# Shield.net
KiCad netlist of a schematic drawn in EAGLE
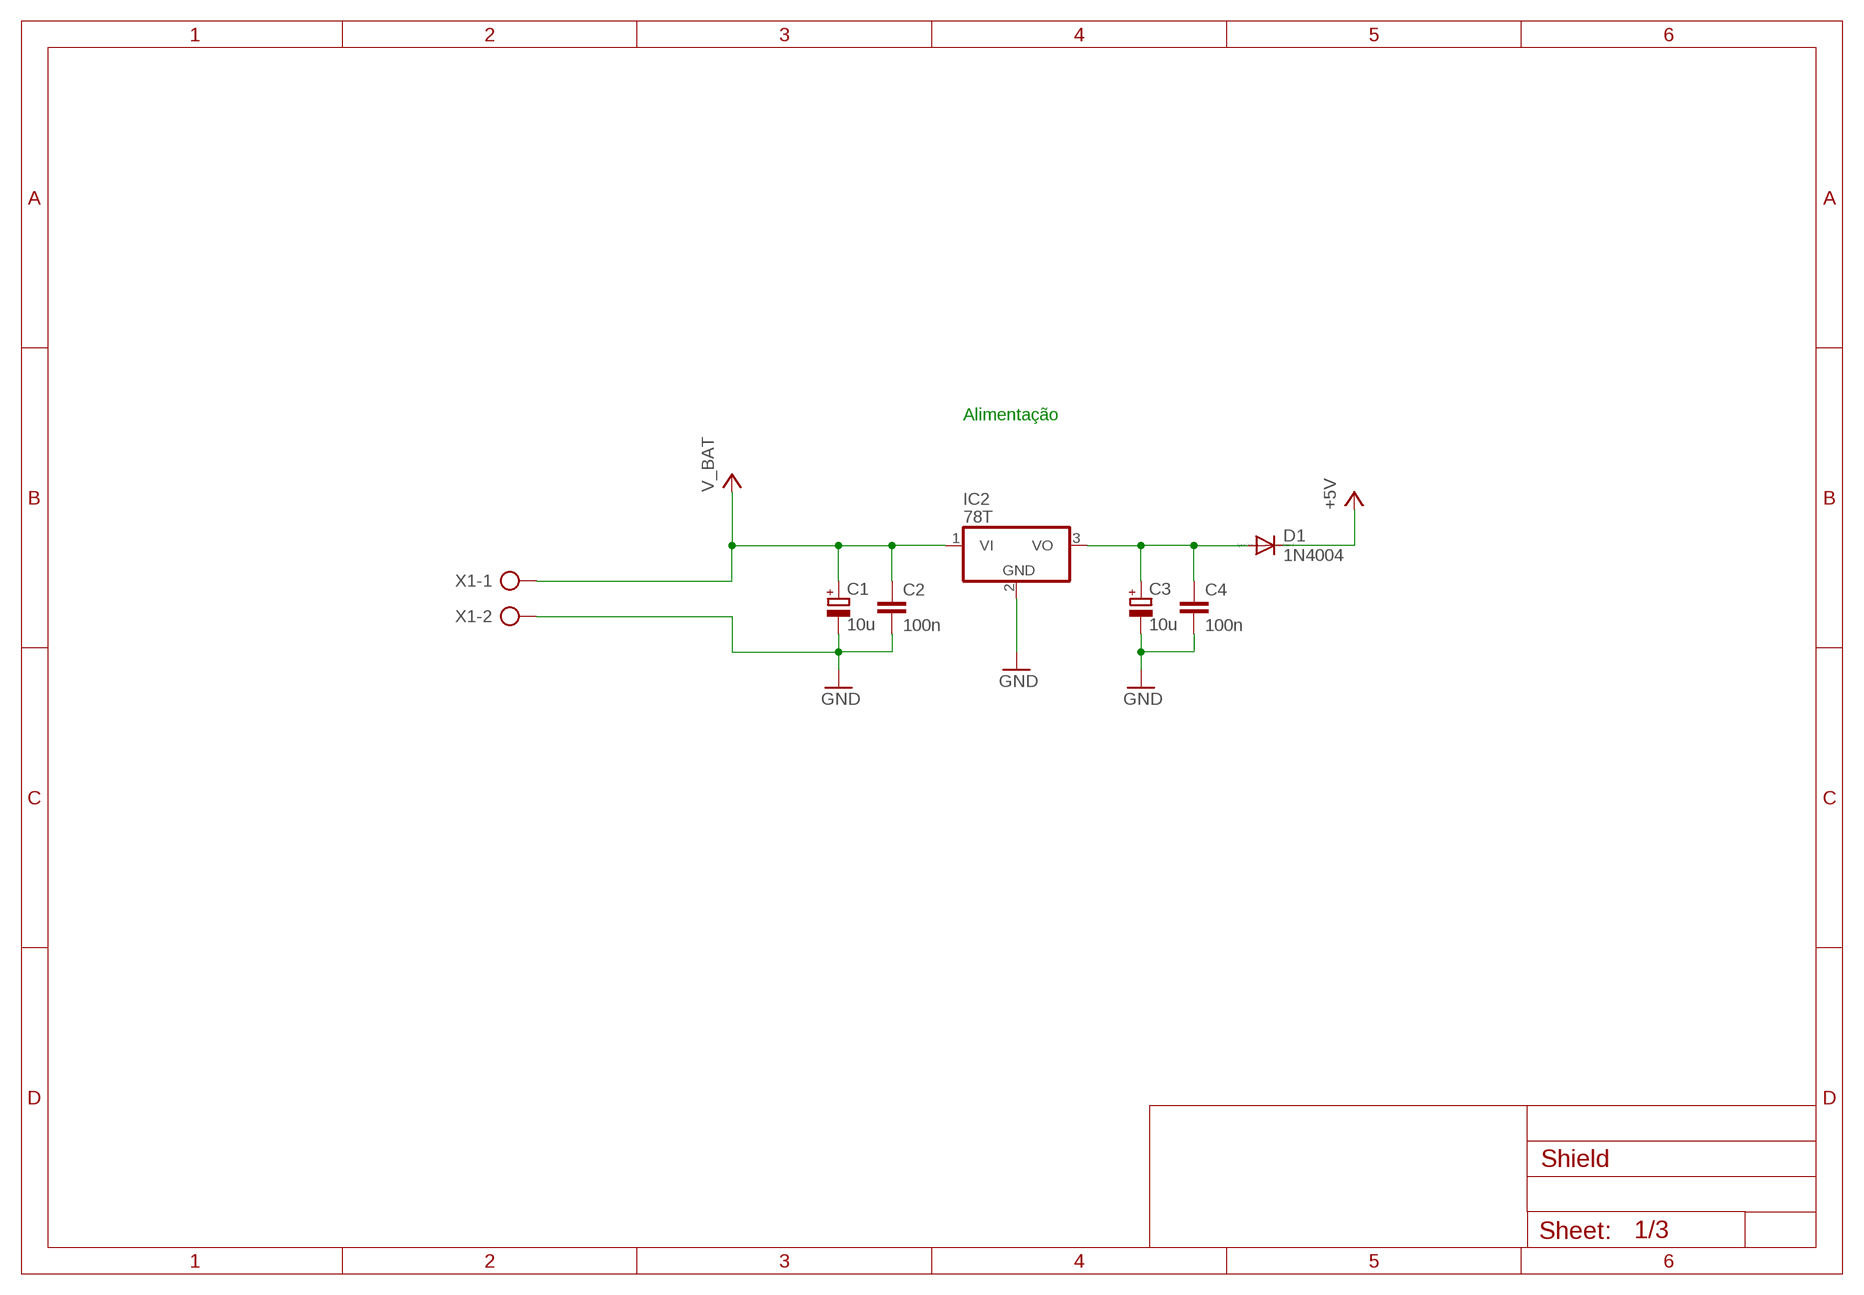
[diagram p0: schematic, sheet 1]
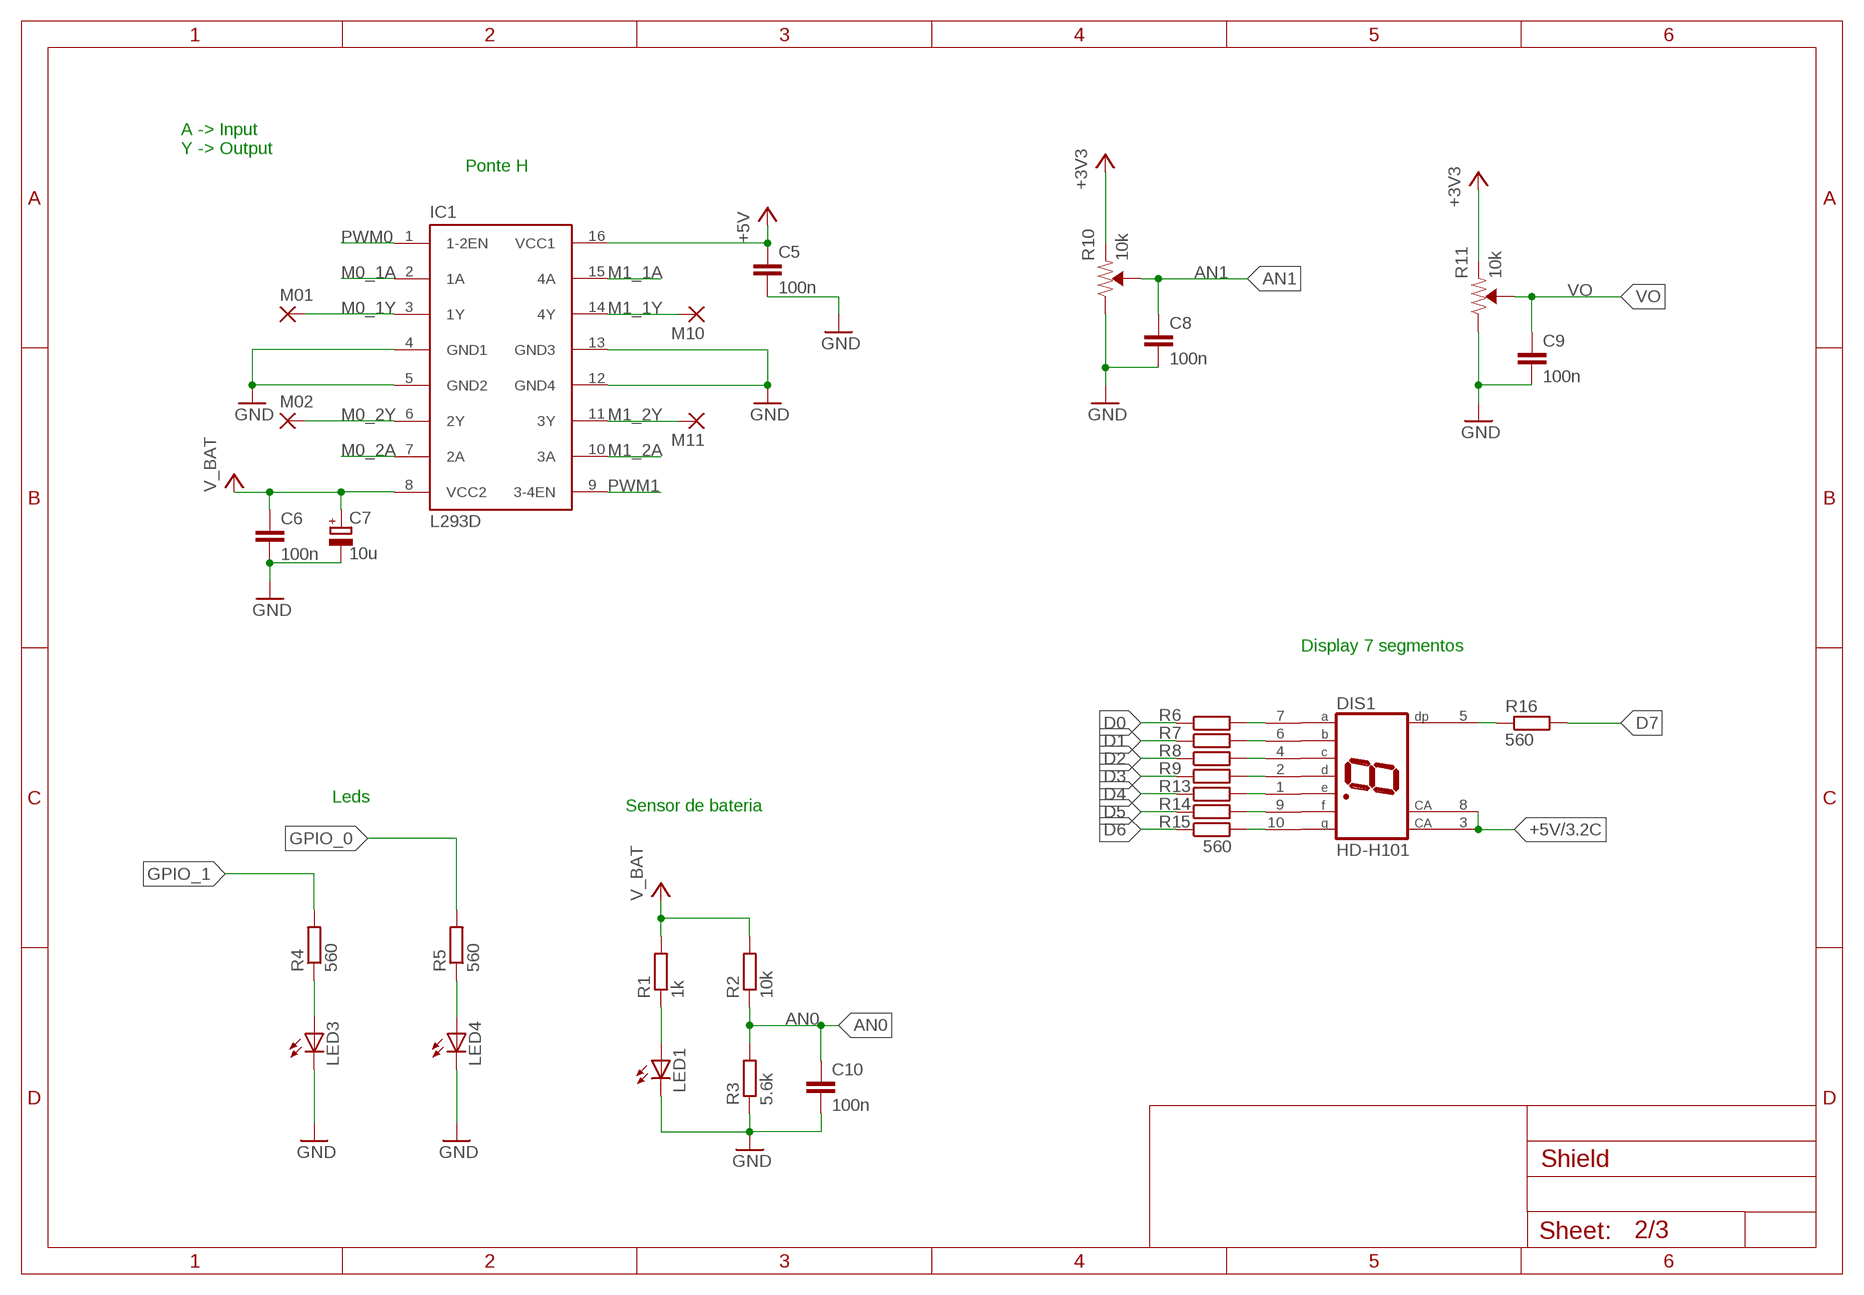
[diagram p1: schematic, sheet 2]
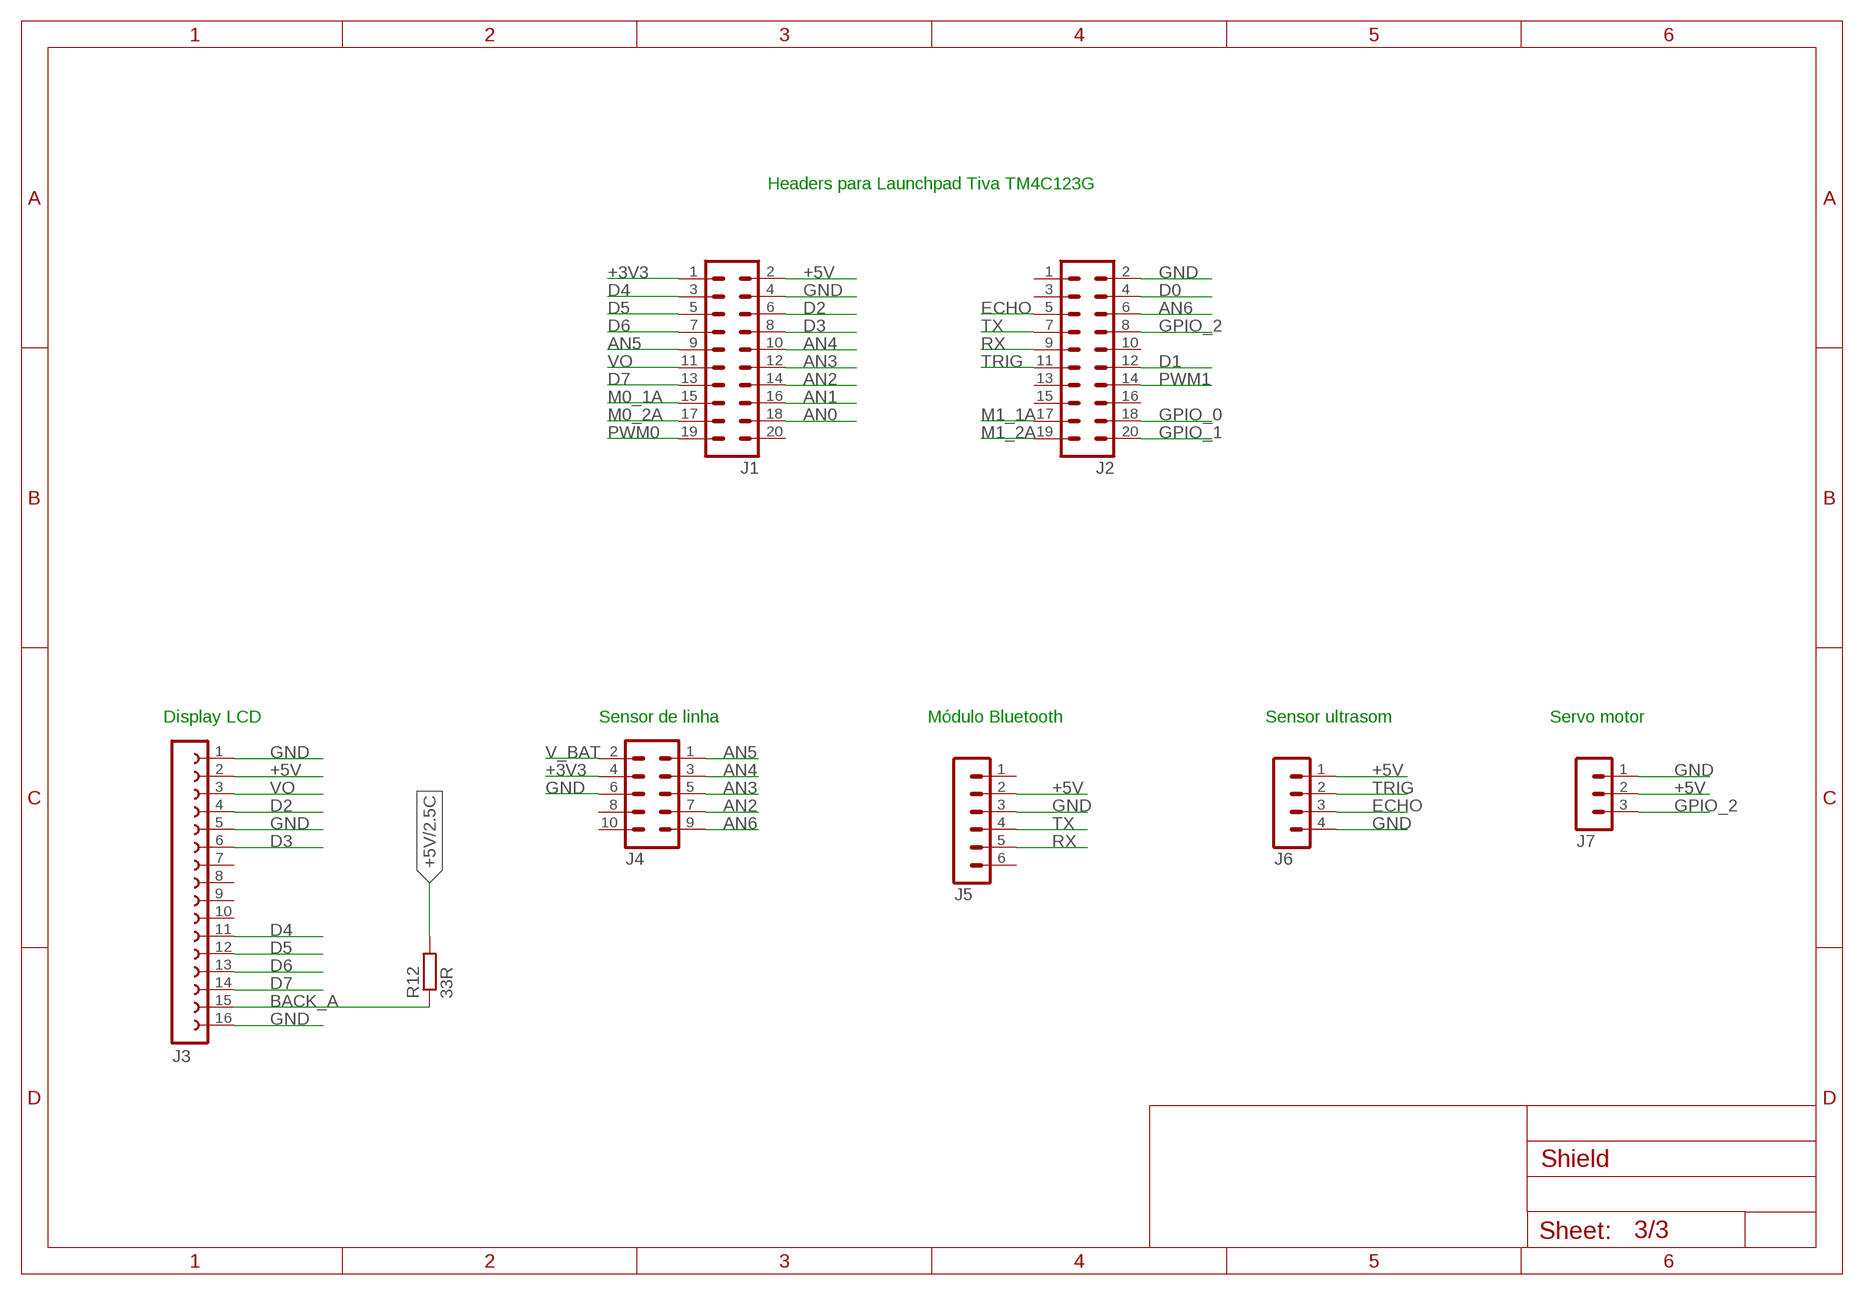
[diagram p2: schematic, sheet 3]

(export (version "E")
  (design (tool "Eeschema 10.0.6"))
  (components
    (comp (ref "C5")
      (value "100n")
      (footprint "eagle-import:C025-024X044")
      (libsource (lib "eagle-import") (part "C-EU025-024X044"))
    )
    (comp (ref "C6")
      (value "100n")
      (footprint "eagle-import:C025-024X044")
      (libsource (lib "eagle-import") (part "C-EU025-024X044"))
    )
    (comp (ref "C7")
      (value "10u")
      (footprint "eagle-import:E2,5-5")
      (libsource (lib "eagle-import") (part "CPOL-EUE2.5-5"))
    )
    (comp (ref "C8")
      (value "100n")
      (footprint "eagle-import:C025-024X044")
      (libsource (lib "eagle-import") (part "C-EU025-024X044"))
    )
    (comp (ref "C9")
      (value "100n")
      (footprint "eagle-import:C025-024X044")
      (libsource (lib "eagle-import") (part "C-EU025-024X044"))
    )
    (comp (ref "C10")
      (value "100n")
      (footprint "eagle-import:C025-024X044")
      (libsource (lib "eagle-import") (part "C-EU025-024X044"))
    )
    (comp (ref "DIS1")
      (value "HD-H101")
      (footprint "eagle-import:HDSP-M")
      (libsource (lib "eagle-import") (part "HD-H101"))
    )
    (comp (ref "IC1")
      (value "L293D")
      (footprint "eagle-import:DIL16")
      (libsource (lib "eagle-import") (part "L293D"))
    )
    (comp (ref "LED1")
      (value "LED5MM")
      (footprint "eagle-import:LED5MM")
      (libsource (lib "eagle-import") (part "LED5MM"))
    )
    (comp (ref "LED3")
      (value "LED5MM")
      (footprint "eagle-import:LED5MM")
      (libsource (lib "eagle-import") (part "LED5MM"))
    )
    (comp (ref "LED4")
      (value "LED5MM")
      (footprint "eagle-import:LED5MM")
      (libsource (lib "eagle-import") (part "LED5MM"))
    )
    (comp (ref "M01")
      (value "2,54/1,1")
      (footprint "eagle-import:2,54_1,1")
      (libsource (lib "eagle-import") (part "2,54/1,1"))
    )
    (comp (ref "M02")
      (value "2,54/1,1")
      (footprint "eagle-import:2,54_1,1")
      (libsource (lib "eagle-import") (part "2,54/1,1"))
    )
    (comp (ref "M10")
      (value "2,54/1,1")
      (footprint "eagle-import:2,54_1,1")
      (libsource (lib "eagle-import") (part "2,54/1,1"))
    )
    (comp (ref "M11")
      (value "2,54/1,1")
      (footprint "eagle-import:2,54_1,1")
      (libsource (lib "eagle-import") (part "2,54/1,1"))
    )
    (comp (ref "R1")
      (value "1k")
      (footprint "eagle-import:0204_7")
      (libsource (lib "eagle-import") (part "R-EU_0204/7"))
    )
    (comp (ref "R2")
      (value "10k")
      (footprint "eagle-import:0204_7")
      (libsource (lib "eagle-import") (part "resistor_348_R-EU_0204/7"))
    )
    (comp (ref "R3")
      (value "5.6k")
      (footprint "eagle-import:0204_7")
      (libsource (lib "eagle-import") (part "R-EU_0204/7"))
    )
    (comp (ref "R4")
      (value "560")
      (footprint "eagle-import:0204_7")
      (libsource (lib "eagle-import") (part "resistor_348_R-EU_0204/7"))
    )
    (comp (ref "R5")
      (value "560")
      (footprint "eagle-import:0204_7")
      (libsource (lib "eagle-import") (part "resistor_348_R-EU_0204/7"))
    )
    (comp (ref "R6")
      (value "560")
      (footprint "eagle-import:0204_7")
      (libsource (lib "eagle-import") (part "R-EU_0204/7"))
    )
    (comp (ref "R7")
      (value "560")
      (footprint "eagle-import:0204_7")
      (libsource (lib "eagle-import") (part "R-EU_0204/7"))
    )
    (comp (ref "R8")
      (value "560")
      (footprint "eagle-import:0204_7")
      (libsource (lib "eagle-import") (part "R-EU_0204/7"))
    )
    (comp (ref "R9")
      (value "560")
      (footprint "eagle-import:0204_7")
      (libsource (lib "eagle-import") (part "R-EU_0204/7"))
    )
    (comp (ref "R10")
      (value "10k")
      (footprint "eagle-import:TRIMPOT-PTH-3386U")
      (libsource (lib "eagle-import") (part "TRIMPOT-PTH-10MM-KNOB-1/2W-10%"))
    )
    (comp (ref "R11")
      (value "10k")
      (footprint "eagle-import:TRIMPOT-PTH-3386U")
      (libsource (lib "eagle-import") (part "TRIMPOT-PTH-10MM-KNOB-1/2W-10%"))
    )
    (comp (ref "R13")
      (value "560")
      (footprint "eagle-import:0204_7")
      (libsource (lib "eagle-import") (part "R-EU_0204/7"))
    )
    (comp (ref "R14")
      (value "560")
      (footprint "eagle-import:0204_7")
      (libsource (lib "eagle-import") (part "R-EU_0204/7"))
    )
    (comp (ref "R15")
      (value "560")
      (footprint "eagle-import:0204_7")
      (libsource (lib "eagle-import") (part "R-EU_0204/7"))
    )
    (comp (ref "R16")
      (value "560")
      (footprint "eagle-import:0204_7")
      (libsource (lib "eagle-import") (part "R-EU_0204/7"))
    )
    (comp (ref "C1")
      (value "10u")
      (footprint "eagle-import:E2,5-5")
      (libsource (lib "eagle-import") (part "CPOL-EUE2.5-5"))
    )
    (comp (ref "C2")
      (value "100n")
      (footprint "eagle-import:C025-024X044")
      (libsource (lib "eagle-import") (part "C-EU025-024X044"))
    )
    (comp (ref "C3")
      (value "10u")
      (footprint "eagle-import:E2,5-5")
      (libsource (lib "eagle-import") (part "CPOL-EUE2.5-5"))
    )
    (comp (ref "C4")
      (value "100n")
      (footprint "eagle-import:C025-024X044")
      (libsource (lib "eagle-import") (part "C-EU025-024X044"))
    )
    (comp (ref "D1")
      (value "1N4004")
      (footprint "eagle-import:DO41-10")
      (libsource (lib "eagle-import") (part "1N4004"))
    )
    (comp (ref "IC2")
      (value "78T")
      (footprint "eagle-import:TO220H")
      (libsource (lib "eagle-import") (part "78T05"))
    )
    (comp (ref "X1")
      (value "AK300/2")
      (footprint "eagle-import:AK300_2")
      (libsource (lib "eagle-import") (part "AK300/2"))
    )
    (comp (ref "J1")
      (value "MA10-2")
      (footprint "eagle-import:MA10-2")
      (libsource (lib "eagle-import") (part "MA10-2"))
    )
    (comp (ref "J2")
      (value "MA10-2")
      (footprint "eagle-import:MA10-2")
      (libsource (lib "eagle-import") (part "MA10-2"))
    )
    (comp (ref "J3")
      (value "FE16-1")
      (footprint "eagle-import:FE16")
      (libsource (lib "eagle-import") (part "FE16-1"))
    )
    (comp (ref "J4")
      (value "MA05-2")
      (footprint "eagle-import:MA05-2")
      (libsource (lib "eagle-import") (part "MA05-2"))
    )
    (comp (ref "J5")
      (value "MA06-1")
      (footprint "eagle-import:MA06-1")
      (libsource (lib "eagle-import") (part "MA06-1"))
    )
    (comp (ref "J6")
      (value "MA04-1")
      (footprint "eagle-import:MA04-1")
      (libsource (lib "eagle-import") (part "MA04-1"))
    )
    (comp (ref "J7")
      (value "MA03-1")
      (footprint "eagle-import:MA03-1")
      (libsource (lib "eagle-import") (part "MA03-1"))
    )
    (comp (ref "R12")
      (value "33R")
      (footprint "eagle-import:0204_7")
      (libsource (lib "eagle-import") (part "R-EU_0204/7"))
    )
  )
  (nets
    (net (code "1") (name "+3V3") (class "Default")
      (node (ref "J1") (pin "1") (pinfunction "1_1") (pintype "passive"))
      (node (ref "J4") (pin "4") (pinfunction "4_4") (pintype "passive"))
      (node (ref "R10") (pin "1") (pinfunction "CCW_1") (pintype "passive"))
      (node (ref "R11") (pin "1") (pinfunction "CCW_1") (pintype "passive"))
    )
    (net (code "2") (name "+5V") (class "Default")
      (node (ref "C5") (pin "1") (pinfunction "1_1") (pintype "passive"))
      (node (ref "D1") (pin "C") (pinfunction "C_C") (pintype "passive"))
      (node (ref "DIS1") (pin "3") (pinfunction "CA_3") (pintype "passive"))
      (node (ref "DIS1") (pin "8") (pinfunction "CA_8") (pintype "passive"))
      (node (ref "IC1") (pin "16") (pinfunction "VCC1_16") (pintype "power_in"))
      (node (ref "J1") (pin "2") (pinfunction "2_2") (pintype "passive"))
      (node (ref "J3") (pin "2") (pinfunction "2_2") (pintype "passive"))
      (node (ref "J5") (pin "2") (pinfunction "2_2") (pintype "passive"))
      (node (ref "J6") (pin "1") (pinfunction "1_1") (pintype "passive"))
      (node (ref "J7") (pin "2") (pinfunction "2_2") (pintype "passive"))
      (node (ref "R12") (pin "2") (pinfunction "2_2") (pintype "passive"))
    )
    (net (code "3") (name "AN0") (class "Default")
      (node (ref "C10") (pin "1") (pinfunction "1_1") (pintype "passive"))
      (node (ref "J1") (pin "18") (pinfunction "18_18") (pintype "passive"))
      (node (ref "R2") (pin "1") (pinfunction "1_1") (pintype "passive"))
      (node (ref "R3") (pin "2") (pinfunction "2_2") (pintype "passive"))
    )
    (net (code "4") (name "AN1") (class "Default")
      (node (ref "C8") (pin "1") (pinfunction "1_1") (pintype "passive"))
      (node (ref "J1") (pin "16") (pinfunction "16_16") (pintype "passive"))
      (node (ref "R10") (pin "2") (pinfunction "WIPER_2") (pintype "passive"))
    )
    (net (code "5") (name "AN2") (class "Default")
      (node (ref "J1") (pin "14") (pinfunction "14_14") (pintype "passive"))
      (node (ref "J4") (pin "7") (pinfunction "7_7") (pintype "passive"))
    )
    (net (code "6") (name "AN3") (class "Default")
      (node (ref "J1") (pin "12") (pinfunction "12_12") (pintype "passive"))
      (node (ref "J4") (pin "5") (pinfunction "5_5") (pintype "passive"))
    )
    (net (code "7") (name "AN4") (class "Default")
      (node (ref "J1") (pin "10") (pinfunction "10_10") (pintype "passive"))
      (node (ref "J4") (pin "3") (pinfunction "3_3") (pintype "passive"))
    )
    (net (code "8") (name "AN5") (class "Default")
      (node (ref "J1") (pin "9") (pinfunction "9_9") (pintype "passive"))
      (node (ref "J4") (pin "1") (pinfunction "1_1") (pintype "passive"))
    )
    (net (code "9") (name "AN6") (class "Default")
      (node (ref "J2") (pin "6") (pinfunction "6_6") (pintype "passive"))
      (node (ref "J4") (pin "9") (pinfunction "9_9") (pintype "passive"))
    )
    (net (code "10") (name "BACK_A") (class "Default")
      (node (ref "J3") (pin "15") (pinfunction "15_15") (pintype "passive"))
      (node (ref "R12") (pin "1") (pinfunction "1_1") (pintype "passive"))
    )
    (net (code "11") (name "D0") (class "Default")
      (node (ref "J2") (pin "4") (pinfunction "4_4") (pintype "passive"))
      (node (ref "R6") (pin "1") (pinfunction "1_1") (pintype "passive"))
    )
    (net (code "12") (name "D1") (class "Default")
      (node (ref "J2") (pin "12") (pinfunction "12_12") (pintype "passive"))
      (node (ref "R7") (pin "1") (pinfunction "1_1") (pintype "passive"))
    )
    (net (code "13") (name "D2") (class "Default")
      (node (ref "J1") (pin "6") (pinfunction "6_6") (pintype "passive"))
      (node (ref "J3") (pin "4") (pinfunction "4_4") (pintype "passive"))
      (node (ref "R8") (pin "1") (pinfunction "1_1") (pintype "passive"))
    )
    (net (code "14") (name "D3") (class "Default")
      (node (ref "J1") (pin "8") (pinfunction "8_8") (pintype "passive"))
      (node (ref "J3") (pin "6") (pinfunction "6_6") (pintype "passive"))
      (node (ref "R9") (pin "1") (pinfunction "1_1") (pintype "passive"))
    )
    (net (code "15") (name "D4") (class "Default")
      (node (ref "J1") (pin "3") (pinfunction "3_3") (pintype "passive"))
      (node (ref "J3") (pin "11") (pinfunction "11_11") (pintype "passive"))
      (node (ref "R13") (pin "1") (pinfunction "1_1") (pintype "passive"))
    )
    (net (code "16") (name "D5") (class "Default")
      (node (ref "J1") (pin "5") (pinfunction "5_5") (pintype "passive"))
      (node (ref "J3") (pin "12") (pinfunction "12_12") (pintype "passive"))
      (node (ref "R14") (pin "1") (pinfunction "1_1") (pintype "passive"))
    )
    (net (code "17") (name "D6") (class "Default")
      (node (ref "J1") (pin "7") (pinfunction "7_7") (pintype "passive"))
      (node (ref "J3") (pin "13") (pinfunction "13_13") (pintype "passive"))
      (node (ref "R15") (pin "1") (pinfunction "1_1") (pintype "passive"))
    )
    (net (code "18") (name "D7") (class "Default")
      (node (ref "J1") (pin "13") (pinfunction "13_13") (pintype "passive"))
      (node (ref "J3") (pin "14") (pinfunction "14_14") (pintype "passive"))
      (node (ref "R16") (pin "2") (pinfunction "2_2") (pintype "passive"))
    )
    (net (code "19") (name "ECHO") (class "Default")
      (node (ref "J2") (pin "5") (pinfunction "5_5") (pintype "passive"))
      (node (ref "J6") (pin "3") (pinfunction "3_3") (pintype "passive"))
    )
    (net (code "20") (name "GND") (class "Default")
      (node (ref "C1") (pin "-") (pinfunction "-_-") (pintype "passive"))
      (node (ref "C10") (pin "2") (pinfunction "2_2") (pintype "passive"))
      (node (ref "C2") (pin "2") (pinfunction "2_2") (pintype "passive"))
      (node (ref "C3") (pin "-") (pinfunction "-_-") (pintype "passive"))
      (node (ref "C4") (pin "2") (pinfunction "2_2") (pintype "passive"))
      (node (ref "C5") (pin "2") (pinfunction "2_2") (pintype "passive"))
      (node (ref "C6") (pin "2") (pinfunction "2_2") (pintype "passive"))
      (node (ref "C7") (pin "-") (pinfunction "-_-") (pintype "passive"))
      (node (ref "C8") (pin "2") (pinfunction "2_2") (pintype "passive"))
      (node (ref "C9") (pin "2") (pinfunction "2_2") (pintype "passive"))
      (node (ref "IC1") (pin "12") (pinfunction "GND4_12") (pintype "power_in"))
      (node (ref "IC1") (pin "13") (pinfunction "GND3_13") (pintype "power_in"))
      (node (ref "IC1") (pin "4") (pinfunction "GND1_4") (pintype "power_in"))
      (node (ref "IC1") (pin "5") (pinfunction "GND2_5") (pintype "power_in"))
      (node (ref "IC2") (pin "2") (pinfunction "GND_2") (pintype "passive"))
      (node (ref "J1") (pin "4") (pinfunction "4_4") (pintype "passive"))
      (node (ref "J2") (pin "2") (pinfunction "2_2") (pintype "passive"))
      (node (ref "J3") (pin "1") (pinfunction "1_1") (pintype "passive"))
      (node (ref "J3") (pin "16") (pinfunction "16_16") (pintype "passive"))
      (node (ref "J3") (pin "5") (pinfunction "5_5") (pintype "passive"))
      (node (ref "J4") (pin "6") (pinfunction "6_6") (pintype "passive"))
      (node (ref "J5") (pin "3") (pinfunction "3_3") (pintype "passive"))
      (node (ref "J6") (pin "4") (pinfunction "4_4") (pintype "passive"))
      (node (ref "J7") (pin "1") (pinfunction "1_1") (pintype "passive"))
      (node (ref "LED1") (pin "K") (pinfunction "C_K") (pintype "passive"))
      (node (ref "LED3") (pin "K") (pinfunction "C_K") (pintype "passive"))
      (node (ref "LED4") (pin "K") (pinfunction "C_K") (pintype "passive"))
      (node (ref "R10") (pin "3") (pinfunction "CW_3") (pintype "passive"))
      (node (ref "R11") (pin "3") (pinfunction "CW_3") (pintype "passive"))
      (node (ref "R3") (pin "1") (pinfunction "1_1") (pintype "passive"))
      (node (ref "X1") (pin "2") (pinfunction "KL_2") (pintype "passive"))
    )
    (net (code "21") (name "GPIO_0") (class "Default")
      (node (ref "J2") (pin "18") (pinfunction "18_18") (pintype "passive"))
      (node (ref "R5") (pin "2") (pinfunction "2_2") (pintype "passive"))
    )
    (net (code "22") (name "GPIO_1") (class "Default")
      (node (ref "J2") (pin "20") (pinfunction "20_20") (pintype "passive"))
      (node (ref "R4") (pin "2") (pinfunction "2_2") (pintype "passive"))
    )
    (net (code "23") (name "GPIO_2") (class "Default")
      (node (ref "J2") (pin "8") (pinfunction "8_8") (pintype "passive"))
      (node (ref "J7") (pin "3") (pinfunction "3_3") (pintype "passive"))
    )
    (net (code "24") (name "M0_1A") (class "Default")
      (node (ref "IC1") (pin "2") (pinfunction "1A_2") (pintype "input"))
      (node (ref "J1") (pin "15") (pinfunction "15_15") (pintype "passive"))
    )
    (net (code "25") (name "M0_1Y") (class "Default")
      (node (ref "IC1") (pin "3") (pinfunction "1Y_3") (pintype "output"))
      (node (ref "M01") (pin "1") (pinfunction "P_1") (pintype "passive"))
    )
    (net (code "26") (name "M0_2A") (class "Default")
      (node (ref "IC1") (pin "7") (pinfunction "2A_7") (pintype "input"))
      (node (ref "J1") (pin "17") (pinfunction "17_17") (pintype "passive"))
    )
    (net (code "27") (name "M0_2Y") (class "Default")
      (node (ref "IC1") (pin "6") (pinfunction "2Y_6") (pintype "output"))
      (node (ref "M02") (pin "1") (pinfunction "P_1") (pintype "passive"))
    )
    (net (code "28") (name "M1_1A") (class "Default")
      (node (ref "IC1") (pin "15") (pinfunction "4A_15") (pintype "input"))
      (node (ref "J2") (pin "17") (pinfunction "17_17") (pintype "passive"))
    )
    (net (code "29") (name "M1_1Y") (class "Default")
      (node (ref "IC1") (pin "14") (pinfunction "4Y_14") (pintype "output"))
      (node (ref "M10") (pin "1") (pinfunction "P_1") (pintype "passive"))
    )
    (net (code "30") (name "M1_2A") (class "Default")
      (node (ref "IC1") (pin "10") (pinfunction "3A_10") (pintype "input"))
      (node (ref "J2") (pin "19") (pinfunction "19_19") (pintype "passive"))
    )
    (net (code "31") (name "M1_2Y") (class "Default")
      (node (ref "IC1") (pin "11") (pinfunction "3Y_11") (pintype "output"))
      (node (ref "M11") (pin "1") (pinfunction "P_1") (pintype "passive"))
    )
    (net (code "32") (name "Net-(DIS1-A)") (class "Default")
      (node (ref "DIS1") (pin "7") (pinfunction "A_7") (pintype "passive"))
      (node (ref "R6") (pin "2") (pinfunction "2_2") (pintype "passive"))
    )
    (net (code "33") (name "Net-(DIS1-B)") (class "Default")
      (node (ref "DIS1") (pin "6") (pinfunction "B_6") (pintype "passive"))
      (node (ref "R7") (pin "2") (pinfunction "2_2") (pintype "passive"))
    )
    (net (code "34") (name "Net-(DIS1-C)") (class "Default")
      (node (ref "DIS1") (pin "4") (pinfunction "C_4") (pintype "passive"))
      (node (ref "R8") (pin "2") (pinfunction "2_2") (pintype "passive"))
    )
    (net (code "35") (name "Net-(DIS1-D)") (class "Default")
      (node (ref "DIS1") (pin "2") (pinfunction "D_2") (pintype "passive"))
      (node (ref "R9") (pin "2") (pinfunction "2_2") (pintype "passive"))
    )
    (net (code "36") (name "Net-(DIS1-DP)") (class "Default")
      (node (ref "DIS1") (pin "5") (pinfunction "DP_5") (pintype "passive"))
      (node (ref "R16") (pin "1") (pinfunction "1_1") (pintype "passive"))
    )
    (net (code "37") (name "Net-(DIS1-E)") (class "Default")
      (node (ref "DIS1") (pin "1") (pinfunction "E_1") (pintype "passive"))
      (node (ref "R13") (pin "2") (pinfunction "2_2") (pintype "passive"))
    )
    (net (code "38") (name "Net-(DIS1-F)") (class "Default")
      (node (ref "DIS1") (pin "9") (pinfunction "F_9") (pintype "passive"))
      (node (ref "R14") (pin "2") (pinfunction "2_2") (pintype "passive"))
    )
    (net (code "39") (name "Net-(DIS1-G)") (class "Default")
      (node (ref "DIS1") (pin "10") (pinfunction "G_10") (pintype "passive"))
      (node (ref "R15") (pin "2") (pinfunction "2_2") (pintype "passive"))
    )
    (net (code "40") (name "Net-(IC2-VO)") (class "Default")
      (node (ref "C3") (pin "+") (pinfunction "+_+") (pintype "passive"))
      (node (ref "C4") (pin "1") (pinfunction "1_1") (pintype "passive"))
      (node (ref "D1") (pin "A") (pinfunction "A_A") (pintype "passive"))
      (node (ref "IC2") (pin "3") (pinfunction "VO_3") (pintype "passive"))
    )
    (net (code "41") (name "Net-(LED1-PadA)") (class "Default")
      (node (ref "LED1") (pin "A") (pinfunction "A_A") (pintype "passive"))
      (node (ref "R1") (pin "1") (pinfunction "1_1") (pintype "passive"))
    )
    (net (code "42") (name "Net-(LED3-PadA)") (class "Default")
      (node (ref "LED3") (pin "A") (pinfunction "A_A") (pintype "passive"))
      (node (ref "R4") (pin "1") (pinfunction "1_1") (pintype "passive"))
    )
    (net (code "43") (name "Net-(LED4-PadA)") (class "Default")
      (node (ref "LED4") (pin "A") (pinfunction "A_A") (pintype "passive"))
      (node (ref "R5") (pin "1") (pinfunction "1_1") (pintype "passive"))
    )
    (net (code "44") (name "PWM0") (class "Default")
      (node (ref "IC1") (pin "1") (pinfunction "1-2EN_1") (pintype "input"))
      (node (ref "J1") (pin "19") (pinfunction "19_19") (pintype "passive"))
    )
    (net (code "45") (name "PWM1") (class "Default")
      (node (ref "IC1") (pin "9") (pinfunction "3-4EN_9") (pintype "input"))
      (node (ref "J2") (pin "14") (pinfunction "14_14") (pintype "passive"))
    )
    (net (code "46") (name "RX") (class "Default")
      (node (ref "J2") (pin "9") (pinfunction "9_9") (pintype "passive"))
      (node (ref "J5") (pin "5") (pinfunction "5_5") (pintype "passive"))
    )
    (net (code "47") (name "TRIG") (class "Default")
      (node (ref "J2") (pin "11") (pinfunction "11_11") (pintype "passive"))
      (node (ref "J6") (pin "2") (pinfunction "2_2") (pintype "passive"))
    )
    (net (code "48") (name "TX") (class "Default")
      (node (ref "J2") (pin "7") (pinfunction "7_7") (pintype "passive"))
      (node (ref "J5") (pin "4") (pinfunction "4_4") (pintype "passive"))
    )
    (net (code "49") (name "VO") (class "Default")
      (node (ref "C9") (pin "1") (pinfunction "1_1") (pintype "passive"))
      (node (ref "J1") (pin "11") (pinfunction "11_11") (pintype "passive"))
      (node (ref "J3") (pin "3") (pinfunction "3_3") (pintype "passive"))
      (node (ref "R11") (pin "2") (pinfunction "WIPER_2") (pintype "passive"))
    )
    (net (code "50") (name "V_BAT") (class "Default")
      (node (ref "C1") (pin "+") (pinfunction "+_+") (pintype "passive"))
      (node (ref "C2") (pin "1") (pinfunction "1_1") (pintype "passive"))
      (node (ref "C6") (pin "1") (pinfunction "1_1") (pintype "passive"))
      (node (ref "C7") (pin "+") (pinfunction "+_+") (pintype "passive"))
      (node (ref "IC1") (pin "8") (pinfunction "VCC2_8") (pintype "power_in"))
      (node (ref "IC2") (pin "1") (pinfunction "VI_1") (pintype "input"))
      (node (ref "J4") (pin "2") (pinfunction "2_2") (pintype "passive"))
      (node (ref "R1") (pin "2") (pinfunction "2_2") (pintype "passive"))
      (node (ref "R2") (pin "2") (pinfunction "2_2") (pintype "passive"))
      (node (ref "X1") (pin "1") (pinfunction "KL_1") (pintype "passive"))
    )
    (net (code "51") (name "unconnected-(J1-Pad20)") (class "Default")
      (node (ref "J1") (pin "20") (pinfunction "20_20") (pintype "passive"))
    )
    (net (code "52") (name "unconnected-(J2-Pad1)") (class "Default")
      (node (ref "J2") (pin "1") (pinfunction "1_1") (pintype "passive"))
    )
    (net (code "53") (name "unconnected-(J2-Pad3)") (class "Default")
      (node (ref "J2") (pin "3") (pinfunction "3_3") (pintype "passive"))
    )
    (net (code "54") (name "unconnected-(J2-Pad10)") (class "Default")
      (node (ref "J2") (pin "10") (pinfunction "10_10") (pintype "passive"))
    )
    (net (code "55") (name "unconnected-(J2-Pad13)") (class "Default")
      (node (ref "J2") (pin "13") (pinfunction "13_13") (pintype "passive"))
    )
    (net (code "56") (name "unconnected-(J2-Pad15)") (class "Default")
      (node (ref "J2") (pin "15") (pinfunction "15_15") (pintype "passive"))
    )
    (net (code "57") (name "unconnected-(J2-Pad16)") (class "Default")
      (node (ref "J2") (pin "16") (pinfunction "16_16") (pintype "passive"))
    )
    (net (code "58") (name "unconnected-(J3-Pad7)") (class "Default")
      (node (ref "J3") (pin "7") (pinfunction "7_7") (pintype "passive"))
    )
    (net (code "59") (name "unconnected-(J3-Pad8)") (class "Default")
      (node (ref "J3") (pin "8") (pinfunction "8_8") (pintype "passive"))
    )
    (net (code "60") (name "unconnected-(J3-Pad9)") (class "Default")
      (node (ref "J3") (pin "9") (pinfunction "9_9") (pintype "passive"))
    )
    (net (code "61") (name "unconnected-(J3-Pad10)") (class "Default")
      (node (ref "J3") (pin "10") (pinfunction "10_10") (pintype "passive"))
    )
    (net (code "62") (name "unconnected-(J4-Pad8)") (class "Default")
      (node (ref "J4") (pin "8") (pinfunction "8_8") (pintype "passive"))
    )
    (net (code "63") (name "unconnected-(J4-Pad10)") (class "Default")
      (node (ref "J4") (pin "10") (pinfunction "10_10") (pintype "passive"))
    )
    (net (code "64") (name "unconnected-(J5-Pad1)") (class "Default")
      (node (ref "J5") (pin "1") (pinfunction "1_1") (pintype "passive"))
    )
    (net (code "65") (name "unconnected-(J5-Pad6)") (class "Default")
      (node (ref "J5") (pin "6") (pinfunction "6_6") (pintype "passive"))
    )
  )
)
